# Sheet1.net
KiCad netlist of a schematic drawn in Altium Designer
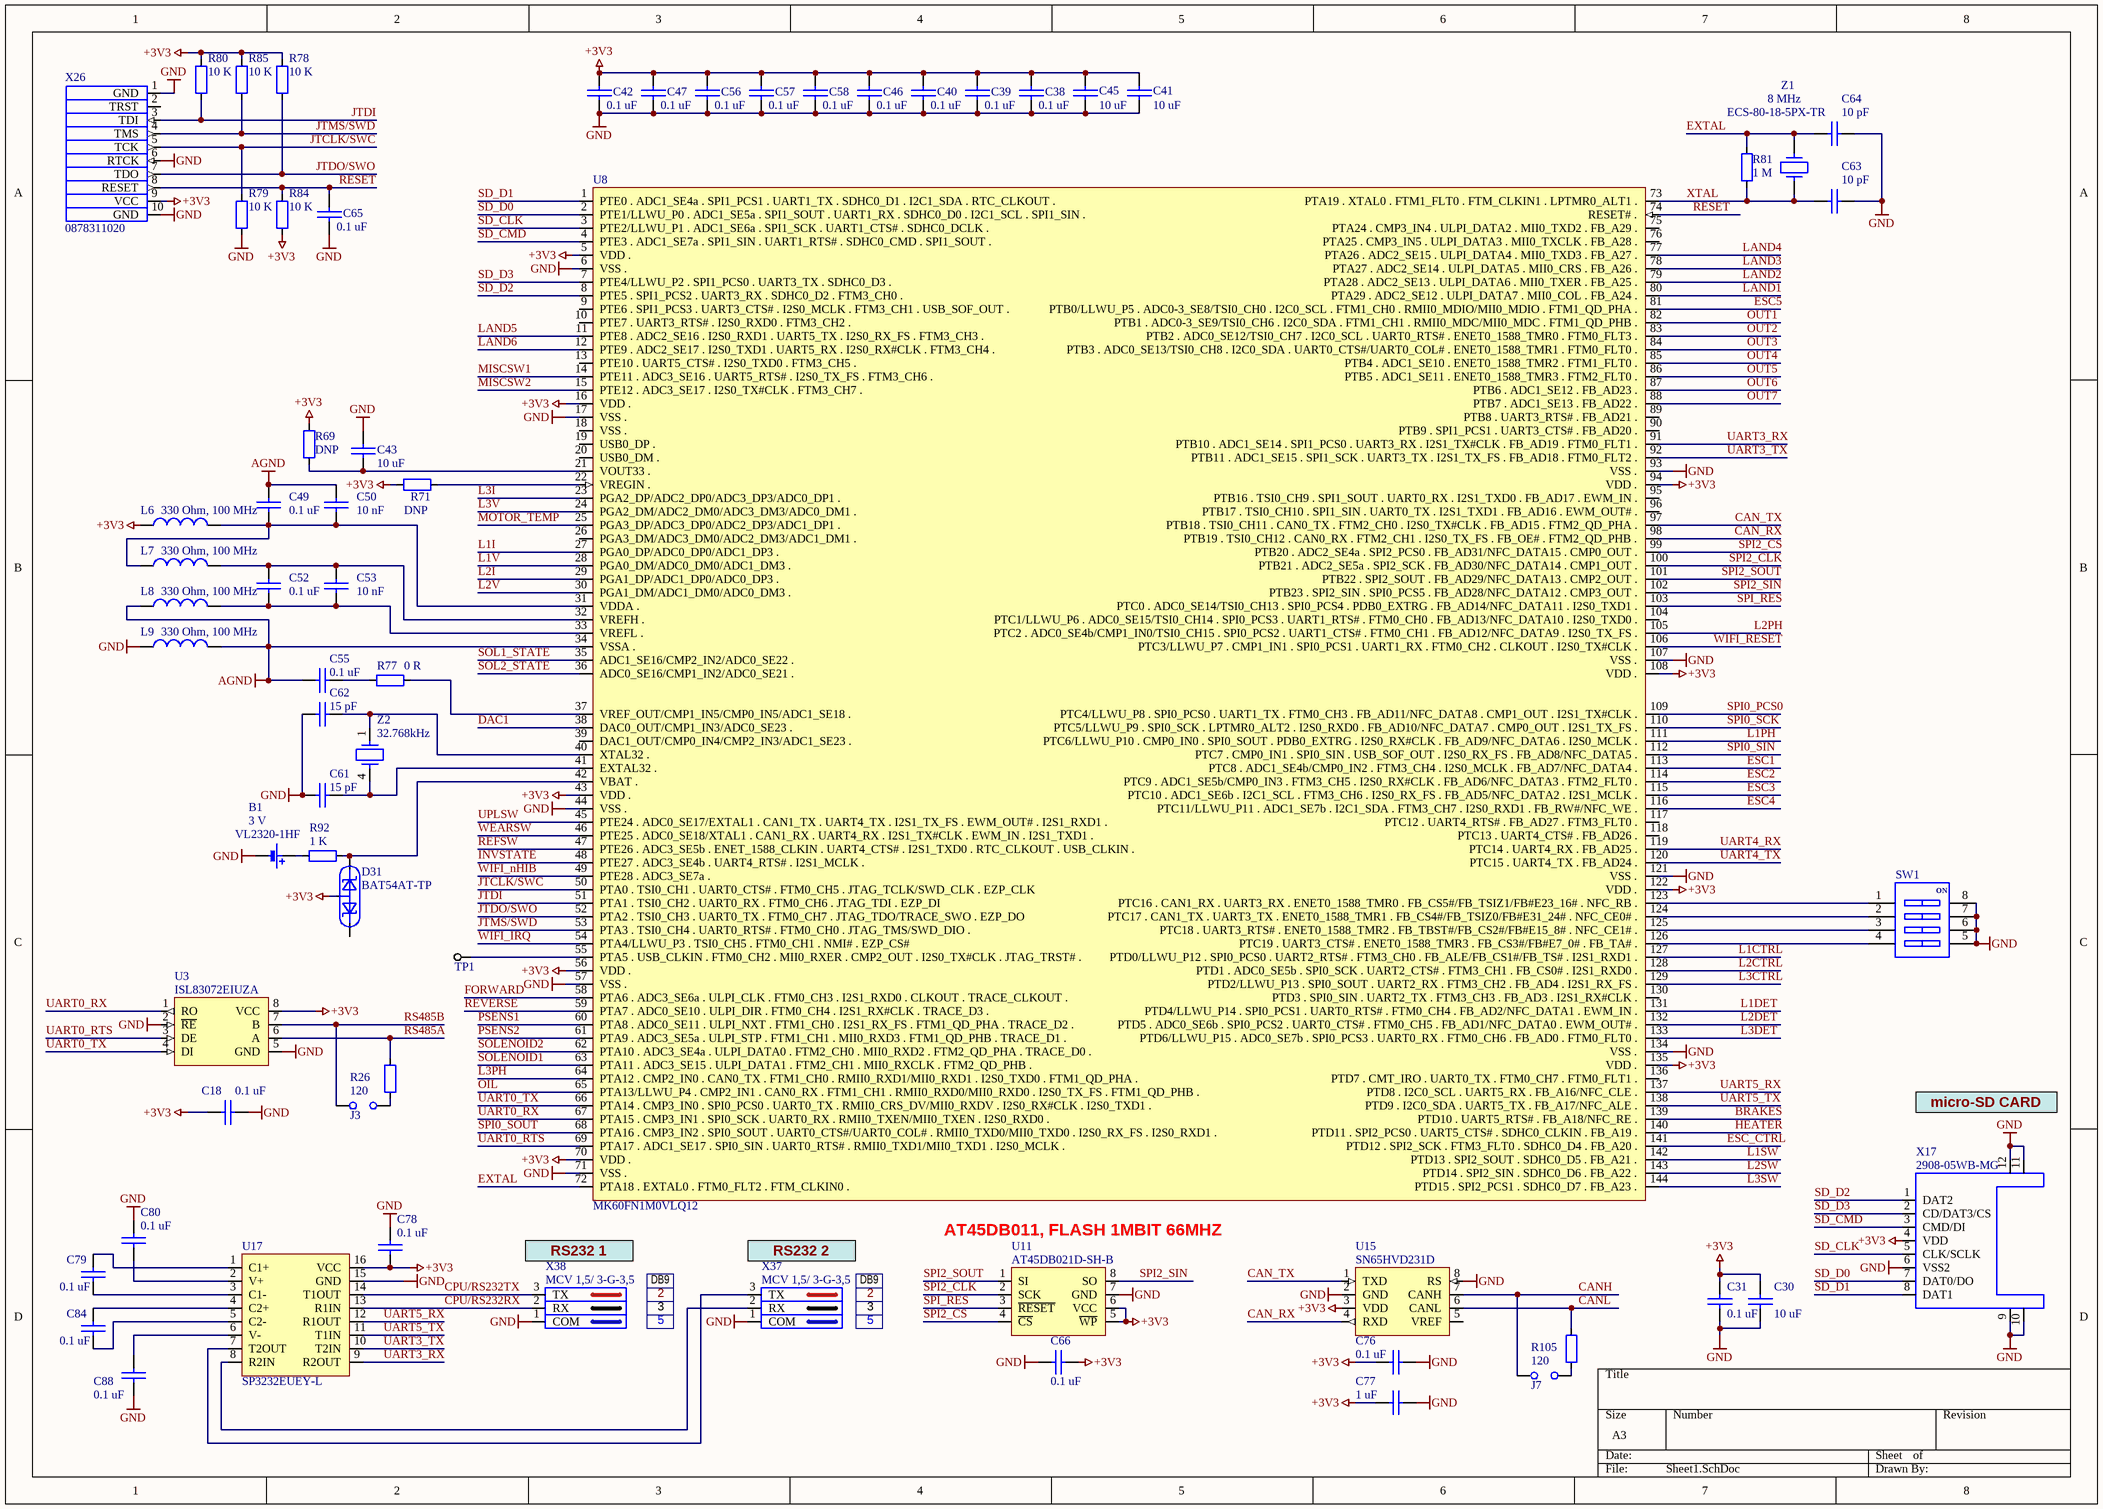
[diagram p0: Sheet1.SchDoc]

(export (version "E")
  (design (tool "Eeschema 10.0.6"))
  (components
    (comp (ref "B1")
      (value "VL2320-1HF")
      (footprint "SANYO ML2430")
      (description "Rechargeable Litium battery, Sanyo, 100 mAh, 3.1 V")
      (fields
        (field (name "PARTNUM") "P083-ND")
        (field (name "MANUFACTURER") "Panasonic - BSG")
        (field (name "ALTIUM_VALUE") "3 V")
      )
      (libsource (lib "*") (part "VL2320-1HF"))
    )
    (comp (ref "C18")
      (value "0.1 uF")
      (footprint "1608[0603]")
      (description "0.1 uF, 25V, 10% , X7R,  0603 SMD MLC Capacitor")
      (fields (field (name "TOLERANCE") "10%") (field (name "MANUFACTURER") "SAMSUNG"))
      (libsource (lib "ea_Capacitors") (part "CVNF100K0603-25"))
    )
    (comp (ref "C30")
      (value "10 uF")
      (footprint "2012[0805]")
      (description "10 uF, 16V, X5R, ±10%, 0805")
      (fields (field (name "MANUFACTURER") "TDK Corporation") (field (name "TOLERANCE") "±10%"))
      (libsource (lib "ea_Capacitors") (part "C2012X5R1C106K/0.85"))
    )
    (comp (ref "C31")
      (value "0.1 uF")
      (footprint "1608[0603]")
      (description "0.1 uF, 25V, 10% , X7R,  0603 SMD MLC Capacitor")
      (fields (field (name "TOLERANCE") "10%") (field (name "MANUFACTURER") "SAMSUNG"))
      (libsource (lib "ea_Capacitors") (part "CVNF100K0603-25"))
    )
    (comp (ref "C38")
      (value "0.1 uF")
      (footprint "1608[0603]")
      (description "0.1 uF, 25V, 10% , X7R,  0603 SMD MLC Capacitor")
      (fields (field (name "TOLERANCE") "10%") (field (name "MANUFACTURER") "SAMSUNG"))
      (libsource (lib "ea_Capacitors") (part "CVNF100K0603-25"))
    )
    (comp (ref "C39")
      (value "0.1 uF")
      (footprint "1608[0603]")
      (description "0.1 uF, 25V, 10% , X7R,  0603 SMD MLC Capacitor")
      (fields (field (name "TOLERANCE") "10%") (field (name "MANUFACTURER") "SAMSUNG"))
      (libsource (lib "ea_Capacitors") (part "CVNF100K0603-25"))
    )
    (comp (ref "C40")
      (value "0.1 uF")
      (footprint "1608[0603]")
      (description "0.1 uF, 25V, 10% , X7R,  0603 SMD MLC Capacitor")
      (fields (field (name "TOLERANCE") "10%") (field (name "MANUFACTURER") "SAMSUNG"))
      (libsource (lib "ea_Capacitors") (part "CVNF100K0603-25"))
    )
    (comp (ref "C41")
      (value "10 uF")
      (footprint "2012[0805]")
      (description "10 uF, 16V, X5R, ±10%, 0805")
      (fields (field (name "MANUFACTURER") "TDK Corporation") (field (name "TOLERANCE") "±10%"))
      (libsource (lib "ea_Capacitors") (part "C2012X5R1C106K/0.85"))
    )
    (comp (ref "C42")
      (value "0.1 uF")
      (footprint "1608[0603]")
      (description "0.1 uF, 25V, 10% , X7R,  0603 SMD MLC Capacitor")
      (fields (field (name "TOLERANCE") "10%") (field (name "MANUFACTURER") "SAMSUNG"))
      (libsource (lib "ea_Capacitors") (part "CVNF100K0603-25"))
    )
    (comp (ref "C43")
      (value "10 uF")
      (footprint "2012[0805]")
      (description "10 uF, 16V, X5R, ±10%, 0805")
      (fields (field (name "MANUFACTURER") "TDK Corporation") (field (name "TOLERANCE") "±10%"))
      (libsource (lib "ea_Capacitors") (part "C2012X5R1C106K/0.85"))
    )
    (comp (ref "C45")
      (value "10 uF")
      (footprint "2012[0805]")
      (description "10 uF, 16V, X5R, ±10%, 0805")
      (fields (field (name "MANUFACTURER") "TDK Corporation") (field (name "TOLERANCE") "±10%"))
      (libsource (lib "ea_Capacitors") (part "C2012X5R1C106K/0.85"))
    )
    (comp (ref "C46")
      (value "0.1 uF")
      (footprint "1608[0603]")
      (description "0.1 uF, 25V, 10% , X7R,  0603 SMD MLC Capacitor")
      (fields (field (name "TOLERANCE") "10%") (field (name "MANUFACTURER") "SAMSUNG"))
      (libsource (lib "ea_Capacitors") (part "CVNF100K0603-25"))
    )
    (comp (ref "C47")
      (value "0.1 uF")
      (footprint "1608[0603]")
      (description "0.1 uF, 25V, 10% , X7R,  0603 SMD MLC Capacitor")
      (fields (field (name "TOLERANCE") "10%") (field (name "MANUFACTURER") "SAMSUNG"))
      (libsource (lib "ea_Capacitors") (part "CVNF100K0603-25"))
    )
    (comp (ref "C49")
      (value "0.1 uF")
      (footprint "1608[0603]")
      (description "0.1 uF, 25V, 10% , X7R,  0603 SMD MLC Capacitor")
      (fields (field (name "TOLERANCE") "10%") (field (name "MANUFACTURER") "SAMSUNG"))
      (libsource (lib "ea_Capacitors") (part "CVNF100K0603-25"))
    )
    (comp (ref "C50")
      (value "10 nF")
      (footprint "1608[0603]")
      (description "10 nF, 50V, 5%, X7R, 0603 SMD MLC Capacitor")
      (fields (field (name "TOLERANCE") "5%") (field (name "MANUFACTURER") "SAMSUNG"))
      (libsource (lib "ea_Capacitors") (part "CVNF010K0603"))
    )
    (comp (ref "C52")
      (value "0.1 uF")
      (footprint "1608[0603]")
      (description "0.1 uF, 25V, 10% , X7R,  0603 SMD MLC Capacitor")
      (fields (field (name "TOLERANCE") "10%") (field (name "MANUFACTURER") "SAMSUNG"))
      (libsource (lib "ea_Capacitors") (part "CVNF100K0603-25"))
    )
    (comp (ref "C53")
      (value "10 nF")
      (footprint "1608[0603]")
      (description "10 nF, 50V, 5%, X7R, 0603 SMD MLC Capacitor")
      (fields (field (name "TOLERANCE") "5%") (field (name "MANUFACTURER") "SAMSUNG"))
      (libsource (lib "ea_Capacitors") (part "CVNF010K0603"))
    )
    (comp (ref "C55")
      (value "0.1 uF")
      (footprint "1608[0603]")
      (description "0.1 uF, 25V, 10% , X7R,  0603 SMD MLC Capacitor")
      (fields (field (name "TOLERANCE") "10%") (field (name "MANUFACTURER") "SAMSUNG"))
      (libsource (lib "ea_Capacitors") (part "CVNF100K0603-25"))
    )
    (comp (ref "C56")
      (value "0.1 uF")
      (footprint "1608[0603]")
      (description "0.1 uF, 25V, 10% , X7R,  0603 SMD MLC Capacitor")
      (fields (field (name "TOLERANCE") "10%") (field (name "MANUFACTURER") "SAMSUNG"))
      (libsource (lib "ea_Capacitors") (part "CVNF100K0603-25"))
    )
    (comp (ref "C57")
      (value "0.1 uF")
      (footprint "1608[0603]")
      (description "0.1 uF, 25V, 10% , X7R,  0603 SMD MLC Capacitor")
      (fields (field (name "TOLERANCE") "10%") (field (name "MANUFACTURER") "SAMSUNG"))
      (libsource (lib "ea_Capacitors") (part "CVNF100K0603-25"))
    )
    (comp (ref "C58")
      (value "0.1 uF")
      (footprint "1608[0603]")
      (description "0.1 uF, 25V, 10% , X7R,  0603 SMD MLC Capacitor")
      (fields (field (name "TOLERANCE") "10%") (field (name "MANUFACTURER") "SAMSUNG"))
      (libsource (lib "ea_Capacitors") (part "CVNF100K0603-25"))
    )
    (comp (ref "C61")
      (value "15 pF")
      (footprint "1608[0603]")
      (description "15 pF, 50V, 5%, NP0, 0603 SMD MLC Capacitor")
      (fields (field (name "MANUFACTURER") "YAGEO AMERICA CORPORATION") (field (name "TOLERANCE") "5%"))
      (libsource (lib "ea_Capacitors") (part "CCPF015K0603"))
    )
    (comp (ref "C62")
      (value "15 pF")
      (footprint "1608[0603]")
      (description "15 pF, 50V, 5%, NP0, 0603 SMD MLC Capacitor")
      (fields (field (name "MANUFACTURER") "YAGEO AMERICA CORPORATION") (field (name "TOLERANCE") "5%"))
      (libsource (lib "ea_Capacitors") (part "CCPF015K0603"))
    )
    (comp (ref "C63")
      (value "10 pF")
      (footprint "1608[0603]")
      (description "10 pF, 50V, 5%, NP0, 0603 SMD MLC Capacitor")
      (fields (field (name "MANUFACTURER") "Kemet") (field (name "TOLERANCE") "5%"))
      (libsource (lib "ea_Capacitors") (part "CCPF010K0603"))
    )
    (comp (ref "C64")
      (value "10 pF")
      (footprint "1608[0603]")
      (description "10 pF, 50V, 5%, NP0, 0603 SMD MLC Capacitor")
      (fields (field (name "MANUFACTURER") "Kemet") (field (name "TOLERANCE") "5%"))
      (libsource (lib "ea_Capacitors") (part "CCPF010K0603"))
    )
    (comp (ref "C65")
      (value "0.1 uF")
      (footprint "1608[0603]")
      (description "0.1 uF, 25V, 10% , X7R,  0603 SMD MLC Capacitor")
      (fields (field (name "TOLERANCE") "10%") (field (name "MANUFACTURER") "SAMSUNG"))
      (libsource (lib "ea_Capacitors") (part "CVNF100K0603-25"))
    )
    (comp (ref "C66")
      (value "0.1 uF")
      (footprint "1608[0603]")
      (description "0.1 uF, 25V, 10% , X7R,  0603 SMD MLC Capacitor")
      (fields (field (name "TOLERANCE") "10%") (field (name "MANUFACTURER") "SAMSUNG"))
      (libsource (lib "ea_Capacitors") (part "CVNF100K0603-25"))
    )
    (comp (ref "C76")
      (value "0.1 uF")
      (footprint "1608[0603]")
      (description "0.1 uF, 25V, 10% , X7R,  0603 SMD MLC Capacitor")
      (fields (field (name "TOLERANCE") "10%") (field (name "MANUFACTURER") "SAMSUNG"))
      (libsource (lib "ea_Capacitors") (part "CVNF100K0603-25"))
    )
    (comp (ref "C77")
      (value "1 uF")
      (footprint "1608[0603]")
      (description "1.0 uF, 6.3V, 10%, X5R, 0603")
      (fields
        (field (name "TOLERANCE") "+-10%")
        (field (name "MANUFACTURER") "Murata Electronics North America")
      )
      (libsource (lib "*") (part "GRM188R60J105KA01D"))
    )
    (comp (ref "C78")
      (value "0.1 uF")
      (footprint "1608[0603]")
      (description "0.1 uF, 25V, 10% , X7R,  0603 SMD MLC Capacitor")
      (fields (field (name "TOLERANCE") "10%") (field (name "MANUFACTURER") "SAMSUNG"))
      (libsource (lib "ea_Capacitors") (part "CVNF100K0603-25"))
    )
    (comp (ref "C79")
      (value "0.1 uF")
      (footprint "1608[0603]")
      (description "0.1 uF, 25V, 10% , X7R,  0603 SMD MLC Capacitor")
      (fields (field (name "TOLERANCE") "10%") (field (name "MANUFACTURER") "SAMSUNG"))
      (libsource (lib "ea_Capacitors") (part "CVNF100K0603-25"))
    )
    (comp (ref "C80")
      (value "0.1 uF")
      (footprint "1608[0603]")
      (description "0.1 uF, 25V, 10% , X7R,  0603 SMD MLC Capacitor")
      (fields (field (name "TOLERANCE") "10%") (field (name "MANUFACTURER") "SAMSUNG"))
      (libsource (lib "ea_Capacitors") (part "CVNF100K0603-25"))
    )
    (comp (ref "C84")
      (value "0.1 uF")
      (footprint "1608[0603]")
      (description "0.1 uF, 25V, 10% , X7R,  0603 SMD MLC Capacitor")
      (fields (field (name "TOLERANCE") "10%") (field (name "MANUFACTURER") "SAMSUNG"))
      (libsource (lib "ea_Capacitors") (part "CVNF100K0603-25"))
    )
    (comp (ref "C88")
      (value "0.1 uF")
      (footprint "1608[0603]")
      (description "0.1 uF, 25V, 10% , X7R,  0603 SMD MLC Capacitor")
      (fields (field (name "TOLERANCE") "10%") (field (name "MANUFACTURER") "SAMSUNG"))
      (libsource (lib "ea_Capacitors") (part "CVNF100K0603-25"))
    )
    (comp (ref "D31")
      (value "BAT54AT-TP")
      (footprint "SOT-523F")
      (description "Schottky Diode, 30 V, 200 mA, common anode, SOT523")
      (fields (field (name "MANUFACTURER") "Micro Commercial Co") (field (name "PARTNUM") "BAT54AT-TPDKR-ND"))
      (libsource (lib "ea_Diodes") (part "BAT54AT-TP"))
    )
    (comp (ref "J3")
      (value "PH1-02-TA-HT")
      (footprint "HDR1X2V")
      (description "2 Pos. 2.54 mm Single Row Through Hole Straight Pin Header")
      (fields (field (name "MANUFACTURER") "ADAM TECH"))
      (libsource (lib "ea_Commutation") (part "Jumper"))
    )
    (comp (ref "J7")
      (value "PH1-02-TA-HT")
      (footprint "HDR1X2V")
      (description "2 Pos. 2.54 mm Single Row Through Hole Straight Pin Header")
      (fields (field (name "MANUFACTURER") "ADAM TECH"))
      (libsource (lib "ea_Commutation") (part "Jumper"))
    )
    (comp (ref "L6")
      (value "330 Ohm, 100 MHz")
      (footprint "0603")
      (description "Ferrite bead, 330 Ohm, 100 MHz,  1.5 A, 0.07 Ohm")
      (fields
        (field (name "MANUFACTURER") "Murata Electronics North America")
        (field (name "PARTNUM") "BLM18SG331TN1D")
      )
      (libsource (lib "*") (part "BLM18SG331TN1D"))
    )
    (comp (ref "L7")
      (value "330 Ohm, 100 MHz")
      (footprint "0603")
      (description "Ferrite bead, 330 Ohm, 100 MHz,  1.5 A, 0.07 Ohm")
      (fields
        (field (name "MANUFACTURER") "Murata Electronics North America")
        (field (name "PARTNUM") "BLM18SG331TN1D")
      )
      (libsource (lib "*") (part "BLM18SG331TN1D"))
    )
    (comp (ref "L8")
      (value "330 Ohm, 100 MHz")
      (footprint "0603")
      (description "Ferrite bead, 330 Ohm, 100 MHz,  1.5 A, 0.07 Ohm")
      (fields
        (field (name "MANUFACTURER") "Murata Electronics North America")
        (field (name "PARTNUM") "BLM18SG331TN1D")
      )
      (libsource (lib "*") (part "BLM18SG331TN1D"))
    )
    (comp (ref "L9")
      (value "330 Ohm, 100 MHz")
      (footprint "0603")
      (description "Ferrite bead, 330 Ohm, 100 MHz,  1.5 A, 0.07 Ohm")
      (fields
        (field (name "MANUFACTURER") "Murata Electronics North America")
        (field (name "PARTNUM") "BLM18SG331TN1D")
      )
      (libsource (lib "*") (part "BLM18SG331TN1D"))
    )
    (comp (ref "R26")
      (value "120")
      (footprint "0603")
      (description "120 R, 1%, 0603, SMD Resistor, Taped")
      (fields (field (name "MANUFACTURER") "Vishay") (field (name "TOLERANCE") "1%"))
      (libsource (lib "ea_Resistors") (part "RL0603E120-1"))
    )
    (comp (ref "R69")
      (value "DNP")
      (footprint "0603")
      (description "DNP, 0603")
      (fields (field (name "Comment") "DNP_0603"))
      (libsource (lib "ea_Resistors") (part "DNP_0603"))
    )
    (comp (ref "R71")
      (value "DNP")
      (footprint "0603")
      (description "DNP, 0603")
      (fields (field (name "Comment") "DNP_0603"))
      (libsource (lib "") (part "DNP_0603_1"))
    )
    (comp (ref "R77")
      (value "0 R")
      (footprint "0603")
      (description "0 R, 5%, 0603, SMD Resistor, Taped")
      (fields (field (name "MANUFACTURER") "YAGEO AMERICA CORPORATION") (field (name "TOLERANCE") "5%"))
      (libsource (lib "ea_Resistors") (part "RL0603E000"))
    )
    (comp (ref "R78")
      (value "10 K")
      (footprint "0603")
      (description "10 K, 1%, 0603, SMD Resistor, Taped")
      (fields (field (name "MANUFACTURER") "Vishay Dale") (field (name "TOLERANCE") "1%"))
      (libsource (lib "ea_Resistors") (part "RL0603K010-1"))
    )
    (comp (ref "R79")
      (value "10 K")
      (footprint "0603")
      (description "10 K, 1%, 0603, SMD Resistor, Taped")
      (fields (field (name "MANUFACTURER") "Vishay Dale") (field (name "TOLERANCE") "1%"))
      (libsource (lib "ea_Resistors") (part "RL0603K010-1"))
    )
    (comp (ref "R80")
      (value "10 K")
      (footprint "0603")
      (description "10 K, 1%, 0603, SMD Resistor, Taped")
      (fields (field (name "MANUFACTURER") "Vishay Dale") (field (name "TOLERANCE") "1%"))
      (libsource (lib "ea_Resistors") (part "RL0603K010-1"))
    )
    (comp (ref "R81")
      (value "1 M")
      (footprint "0603")
      (description "1 M, 1%, 0603, SMD Resistor, Taped")
      (fields (field (name "MANUFACTURER") "YAGEO AMERICA CORPORATION") (field (name "TOLERANCE") "1%"))
      (libsource (lib "ea_Resistors") (part "RC0603FR-071ML"))
    )
    (comp (ref "R84")
      (value "10 K")
      (footprint "0603")
      (description "10 K, 1%, 0603, SMD Resistor, Taped")
      (fields (field (name "MANUFACTURER") "Vishay Dale") (field (name "TOLERANCE") "1%"))
      (libsource (lib "ea_Resistors") (part "RL0603K010-1"))
    )
    (comp (ref "R85")
      (value "10 K")
      (footprint "0603")
      (description "10 K, 1%, 0603, SMD Resistor, Taped")
      (fields (field (name "MANUFACTURER") "Vishay Dale") (field (name "TOLERANCE") "1%"))
      (libsource (lib "ea_Resistors") (part "RL0603K010-1"))
    )
    (comp (ref "R92")
      (value "1 K")
      (footprint "0603")
      (description "1 K, 1%, 0603, SMD Resistor, Taped")
      (fields (field (name "MANUFACTURER") "YAGEO AMERICA CORPORATION") (field (name "TOLERANCE") "1%"))
      (libsource (lib "ea_Resistors") (part "RL0603K001-1"))
    )
    (comp (ref "R105")
      (value "120")
      (footprint "0603")
      (description "120 R, 1%, 0603, SMD Resistor, Taped")
      (fields (field (name "MANUFACTURER") "Vishay") (field (name "TOLERANCE") "1%"))
      (libsource (lib "ea_Resistors") (part "RL0603E120-1"))
    )
    (comp (ref "SW1")
      (value "MCDHN-04F-T-V")
      (footprint "MCDHN-04F-T-V")
      (description "SWITCH, DIP, SMD, 4 WAY, 1.27mm")
      (fields (field (name "MANUFACTURER") "MULTICOMP") (field (name "PARTNUM") "1605479"))
      (libsource (lib "ea_Commutation") (part "MCDHN-04F-T-V"))
    )
    (comp (ref "TP1")
      (value "Test_point 0.7 мм")
      (footprint "Test point 0.7 мм")
      (libsource (lib "ea_Connectors") (part "Test_point 0.7 мм"))
    )
    (comp (ref "U3")
      (value "ISL83072EIUZA")
      (footprint "MSOP 8")
      (description "RS485/422 Transc. 3..3.6V  , -40..+85 C,10-MSOP")
      (fields (field (name "MANUFACTURER") "Intersil") (field (name "PARTNUM") "ISL83072EIUZA-TCT-ND"))
      (libsource (lib "ea_IC_Interfaces") (part "ISL3178EIUZ"))
    )
    (comp (ref "U8")
      (value "MK60FN1M0VLQ12")
      (footprint "ea_TQFP:LQFP144")
      (description "MK60 Series 32 Bit 1 MB Flash 128 KB Ram 120 Mhz Microcontroller - LQFP-144")
      (fields (field (name "MANUFACTURER") "Freescale"))
      (libsource (lib "ea_IC_CPU") (part "MK60FN1M0VLQ12"))
    )
    (comp (ref "U11")
      (value "AT45DB021D-SH-B")
      (footprint "SO-8  wide")
      (description "IC DATAFLASH 1MBIT 2.7 V ~ 3.6 V 8-SOIC")
      (fields (field (name "MANUFACTURER") "Adesto Technologies") (field (name "PARTNUM") "1265-1033-1-ND"))
      (libsource (lib "ea_IC_NOR_NAND_FLASH") (part "AT45DB011D-SH-T"))
    )
    (comp (ref "U15")
      (value "SN65HVD231D")
      (footprint "SO-8")
      (description "3.3-V CAN TRANSCEIVERS SO-8")
      (fields (field (name "MANUFACTURER") "Texas Instruments") (field (name "PARTNUM") "296-12206-5-ND"))
      (libsource (lib "ea_IC_Interfaces") (part "SN65HVD231D"))
    )
    (comp (ref "U17")
      (value "SP3232EUEY-L")
      (footprint "TSOP65P640-16AM")
      (description "IC TXRX RS232 ESD TRUE, 1 Mbps, -40+85C, 16TSSOP")
      (fields (field (name "MANUFACTURER") "Exar Corporation") (field (name "PARTNUM") "1016-1510-5-ND"))
      (libsource (lib "ea_IC_Interfaces") (part "SP3232EUEY-L"))
    )
    (comp (ref "X17")
      (value "2908-05WB-MG")
      (footprint "2908-05WB-MG")
      (description "microSD cadr holder")
      (fields
        (field (name "MANUFACTURER") "Amphenol Commercial Products")
        (field (name "PARTNUM") "101-00660-68-6-1-ND")
      )
      (libsource (lib "ea_CARD_holders") (part "2908-05WB-MG"))
    )
    (comp (ref "X26")
      (value "0878311020")
      (footprint "878311020 MGRID WALL HDR SMD")
      (description "JTAG, CONN HEADER 10POS 2MM VERT SMD")
      (fields (field (name "MANUFACTURER") "Molex Inc") (field (name "PARTNUM") "WM18639-ND"))
      (libsource (lib "ea_Connectors") (part "0878321020"))
    )
    (comp (ref "X37")
      (value "MCV 1,5/ 3-G-3,5")
      (footprint "mcv1.5-3-g_3.5")
      (description "Header, 8 A, 160 V, 3.5 mm pitch, 3 pos")
      (fields (field (name "MANUFACTURER") "Phoenix Contact") (field (name "PARTNUM") "1843619"))
      (libsource (lib "ea_Connectors") (part "MCV1.5/3-G-3.5"))
    )
    (comp (ref "X38")
      (value "MCV 1,5/ 3-G-3,5")
      (footprint "mcv1.5-3-g_3.5")
      (description "Header, 8 A, 160 V, 3.5 mm pitch, 3 pos")
      (fields (field (name "MANUFACTURER") "Phoenix Contact") (field (name "PARTNUM") "1843619"))
      (libsource (lib "ea_Connectors") (part "MCV1.5/3-G-3.5"))
    )
    (comp (ref "Z1")
      (value "ECS-80-18-5PX-TR")
      (footprint "Quartz Crystal SMU4")
      (fields
        (field (name "MANUFACTURER") "ECS Inc.")
        (field (name "ALTIUM_VALUE") "8 MHz")
        (field (name "PARTNUM") "XC1271CT-ND")
      )
      (libsource (lib "*") (part "ECS-80-18-5PX-TR"))
    )
    (comp (ref "Z2")
      (value "32.768kHz")
      (footprint "CM200S")
      (description "Crystal 32.768 kHz ±20 ppm 6 pF -40 to +85 °C SMT Tuning Fork Crystal")
      (fields
        (field (name "MANUFACTURER") "CITIZEN FINETECH MIYOTA")
        (field (name "PARTNUM") "CM200C32768DZBT")
      )
      (libsource (lib "*") (part "MC306-32,768"))
    )
  )
  (nets
    (net (code "1") (name "+3V3") (class "Default")
      (node (ref "C18") (pin "1") (pinfunction "1_1") (pintype "passive"))
      (node (ref "C30") (pin "1") (pinfunction "1_1") (pintype "passive"))
      (node (ref "C31") (pin "1") (pinfunction "1_1") (pintype "passive"))
      (node (ref "C38") (pin "2") (pinfunction "2_2") (pintype "passive"))
      (node (ref "C39") (pin "2") (pinfunction "2_2") (pintype "passive"))
      (node (ref "C40") (pin "2") (pinfunction "2_2") (pintype "passive"))
      (node (ref "C41") (pin "1") (pinfunction "1_1") (pintype "passive"))
      (node (ref "C42") (pin "2") (pinfunction "2_2") (pintype "passive"))
      (node (ref "C45") (pin "1") (pinfunction "1_1") (pintype "passive"))
      (node (ref "C46") (pin "2") (pinfunction "2_2") (pintype "passive"))
      (node (ref "C47") (pin "2") (pinfunction "2_2") (pintype "passive"))
      (node (ref "C56") (pin "2") (pinfunction "2_2") (pintype "passive"))
      (node (ref "C57") (pin "2") (pinfunction "2_2") (pintype "passive"))
      (node (ref "C58") (pin "2") (pinfunction "2_2") (pintype "passive"))
      (node (ref "C66") (pin "1") (pinfunction "1_1") (pintype "passive"))
      (node (ref "C76") (pin "1") (pinfunction "1_1") (pintype "passive"))
      (node (ref "C77") (pin "1") (pinfunction "1_1") (pintype "passive"))
      (node (ref "C78") (pin "1") (pinfunction "1_1") (pintype "passive"))
      (node (ref "D31") (pin "3") (pintype "passive"))
      (node (ref "L6") (pin "1") (pinfunction "1_1") (pintype "passive"))
      (node (ref "R69") (pin "2") (pinfunction "2_2") (pintype "passive"))
      (node (ref "R71") (pin "1") (pinfunction "1_1") (pintype "passive"))
      (node (ref "R78") (pin "2") (pinfunction "2_2") (pintype "passive"))
      (node (ref "R80") (pin "2") (pinfunction "2_2") (pintype "passive"))
      (node (ref "R84") (pin "1") (pinfunction "1_1") (pintype "passive"))
      (node (ref "R85") (pin "2") (pinfunction "2_2") (pintype "passive"))
      (node (ref "U11") (pin "5") (pinfunction "~{WP}_5") (pintype "passive"))
      (node (ref "U11") (pin "6") (pinfunction "VCC_6") (pintype "passive"))
      (node (ref "U15") (pin "3") (pinfunction "VDD_3") (pintype "power_in"))
      (node (ref "U17") (pin "16") (pinfunction "VCC_16") (pintype "passive"))
      (node (ref "U3") (pin "8") (pinfunction "VCC_8") (pintype "power_in"))
      (node (ref "U8") (pin "108") (pinfunction "VDD_._108") (pintype "power_in"))
      (node (ref "U8") (pin "122") (pinfunction "VDD_._122") (pintype "power_in"))
      (node (ref "U8") (pin "135") (pinfunction "VDD_._135") (pintype "power_in"))
      (node (ref "U8") (pin "16") (pinfunction "VDD_._16") (pintype "power_in"))
      (node (ref "U8") (pin "43") (pinfunction "VDD_._43") (pintype "power_in"))
      (node (ref "U8") (pin "5") (pinfunction "VDD_._5") (pintype "power_in"))
      (node (ref "U8") (pin "56") (pinfunction "VDD_._56") (pintype "power_in"))
      (node (ref "U8") (pin "70") (pinfunction "VDD_._70") (pintype "power_in"))
      (node (ref "U8") (pin "94") (pinfunction "VDD_._94") (pintype "power_in"))
      (node (ref "X17") (pin "4") (pinfunction "VDD_4") (pintype "passive"))
      (node (ref "X26") (pin "9") (pinfunction "VCC_9") (pintype "power_in"))
    )
    (net (code "2") (name "/BRAKES") (class "Default")
      (node (ref "U8") (pin "139") (pinfunction "PTD10_._UART5_RTS#_._FB_A18/NFC_RE_._139") (pintype "bidirectional"))
    )
    (net (code "3") (name "/CANH") (class "Default")
      (node (ref "J7") (pin "1") (pinfunction "1_1") (pintype "passive"))
      (node (ref "U15") (pin "7") (pinfunction "CANH_7") (pintype "bidirectional"))
    )
    (net (code "4") (name "/CANL") (class "Default")
      (node (ref "R105") (pin "2") (pinfunction "2_2") (pintype "passive"))
      (node (ref "U15") (pin "6") (pinfunction "CANL_6") (pintype "bidirectional"))
    )
    (net (code "5") (name "/CAN_RX") (class "Default")
      (node (ref "U15") (pin "4") (pinfunction "RXD_4") (pintype "output"))
      (node (ref "U8") (pin "98") (pinfunction "PTB19_._TSI0_CH12_._CAN0_RX_._FTM2_CH1_._I2S0_TX_FS_._FB_OE#_._FTM2_QD_PHB_._98") (pintype "bidirectional"))
    )
    (net (code "6") (name "/CAN_TX") (class "Default")
      (node (ref "U15") (pin "1") (pinfunction "TXD_1") (pintype "input"))
      (node (ref "U8") (pin "97") (pinfunction "PTB18_._TSI0_CH11_._CAN0_TX_._FTM2_CH0_._I2S0_TX#CLK_._FB_AD15_._FTM2_QD_PHA_._97") (pintype "bidirectional"))
    )
    (net (code "7") (name "/CPU{slash}RS232RX") (class "Default")
      (node (ref "U17") (pin "13") (pinfunction "R1IN_13") (pintype "passive"))
      (node (ref "X38") (pin "2") (pinfunction "RX_2") (pintype "passive"))
    )
    (net (code "8") (name "/CPU{slash}RS232TX") (class "Default")
      (node (ref "U17") (pin "14") (pinfunction "T1OUT_14") (pintype "passive"))
      (node (ref "X38") (pin "3") (pinfunction "TX_3") (pintype "passive"))
    )
    (net (code "9") (name "/DAC1") (class "Default")
      (node (ref "U8") (pin "38") (pinfunction "DAC0_OUT/CMP1_IN3/ADC0_SE23_._38") (pintype "bidirectional"))
    )
    (net (code "10") (name "/ESC1") (class "Default")
      (node (ref "U8") (pin "113") (pinfunction "PTC8_._ADC1_SE4b/CMP0_IN2_._FTM3_CH4_._I2S0_MCLK_._FB_AD7/NFC_DATA4_._113") (pintype "bidirectional"))
    )
    (net (code "11") (name "/ESC2") (class "Default")
      (node (ref "U8") (pin "114") (pinfunction "PTC9_._ADC1_SE5b/CMP0_IN3_._FTM3_CH5_._I2S0_RX#CLK_._FB_AD6/NFC_DATA3_._FTM2_FLT0_._114") (pintype "bidirectional"))
    )
    (net (code "12") (name "/ESC3") (class "Default")
      (node (ref "U8") (pin "115") (pinfunction "PTC10_._ADC1_SE6b_._I2C1_SCL_._FTM3_CH6_._I2S0_RX_FS_._FB_AD5/NFC_DATA2_._I2S1_MCLK_._115") (pintype "bidirectional"))
    )
    (net (code "13") (name "/ESC4") (class "Default")
      (node (ref "U8") (pin "116") (pinfunction "PTC11/LLWU_P11_._ADC1_SE7b_._I2C1_SDA_._FTM3_CH7_._I2S0_RXD1_._FB_RW#/NFC_WE_._116") (pintype "bidirectional"))
    )
    (net (code "14") (name "/ESC5") (class "Default")
      (node (ref "U8") (pin "81") (pinfunction "PTB0/LLWU_P5_._ADC0-3_SE8/TSI0_CH0_._I2C0_SCL_._FTM1_CH0_._RMII0_MDIO/MII0_MDIO_._FTM1_QD_PHA_._81") (pintype "bidirectional"))
    )
    (net (code "15") (name "/ESC_CTRL") (class "Default")
      (node (ref "U8") (pin "141") (pinfunction "PTD12_._SPI2_SCK_._FTM3_FLT0_._SDHC0_D4_._FB_A20_._141") (pintype "bidirectional"))
    )
    (net (code "16") (name "/EXTAL") (class "Default")
      (node (ref "C64") (pin "1") (pinfunction "1_1") (pintype "passive"))
      (node (ref "R81") (pin "2") (pinfunction "2_2") (pintype "passive"))
      (node (ref "U8") (pin "72") (pinfunction "PTA18_._EXTAL0_._FTM0_FLT2_._FTM_CLKIN0_._72") (pintype "bidirectional"))
      (node (ref "Z1") (pin "2") (pinfunction "2_2") (pintype "passive"))
    )
    (net (code "17") (name "/FORWARD") (class "Default")
      (node (ref "U8") (pin "58") (pinfunction "PTA6_._ADC3_SE6a_._ULPI_CLK_._FTM0_CH3_._I2S1_RXD0_._CLKOUT_._TRACE_CLKOUT_._58") (pintype "bidirectional"))
    )
    (net (code "18") (name "/HEATER") (class "Default")
      (node (ref "U8") (pin "140") (pinfunction "PTD11_._SPI2_PCS0_._UART5_CTS#_._SDHC0_CLKIN_._FB_A19_._140") (pintype "bidirectional"))
    )
    (net (code "19") (name "/INVSTATE") (class "Default")
      (node (ref "U8") (pin "48") (pinfunction "PTE27_._ADC3_SE4b_._UART4_RTS#_._I2S1_MCLK_._48") (pintype "bidirectional"))
    )
    (net (code "20") (name "/JTCLK{slash}SWC") (class "Default")
      (node (ref "R79") (pin "2") (pinfunction "2_2") (pintype "passive"))
      (node (ref "U8") (pin "50") (pinfunction "PTA0_._TSI0_CH1_._UART0_CTS#_._FTM0_CH5_._JTAG_TCLK/SWD_CLK_._EZP_CLK_50") (pintype "bidirectional"))
      (node (ref "X26") (pin "5") (pinfunction "TCK_5") (pintype "output"))
    )
    (net (code "21") (name "/JTDI") (class "Default")
      (node (ref "R80") (pin "1") (pinfunction "1_1") (pintype "passive"))
      (node (ref "U8") (pin "51") (pinfunction "PTA1_._TSI0_CH2_._UART0_RX_._FTM0_CH6_._JTAG_TDI_._EZP_DI_51") (pintype "bidirectional"))
      (node (ref "X26") (pin "3") (pinfunction "TDI_3") (pintype "input"))
    )
    (net (code "22") (name "/JTDO{slash}SWO") (class "Default")
      (node (ref "R78") (pin "1") (pinfunction "1_1") (pintype "passive"))
      (node (ref "U8") (pin "52") (pinfunction "PTA2_._TSI0_CH3_._UART0_TX_._FTM0_CH7_._JTAG_TDO/TRACE_SWO_._EZP_DO_52") (pintype "bidirectional"))
      (node (ref "X26") (pin "7") (pinfunction "TDO_7") (pintype "output"))
    )
    (net (code "23") (name "/JTMS{slash}SWD") (class "Default")
      (node (ref "R85") (pin "1") (pinfunction "1_1") (pintype "passive"))
      (node (ref "U8") (pin "53") (pinfunction "PTA3_._TSI0_CH4_._UART0_RTS#_._FTM0_CH0_._JTAG_TMS/SWD_DIO_._53") (pintype "bidirectional"))
      (node (ref "X26") (pin "4") (pinfunction "TMS_4") (pintype "output"))
    )
    (net (code "24") (name "/L1CTRL") (class "Default")
      (node (ref "U8") (pin "127") (pinfunction "PTD0/LLWU_P12_._SPI0_PCS0_._UART2_RTS#_._FTM3_CH0_._FB_ALE/FB_CS1#/FB_TS#_._I2S1_RXD1_._127") (pintype "bidirectional"))
    )
    (net (code "25") (name "/L1DET") (class "Default")
      (node (ref "U8") (pin "131") (pinfunction "PTD4/LLWU_P14_._SPI0_PCS1_._UART0_RTS#_._FTM0_CH4_._FB_AD2/NFC_DATA1_._EWM_IN_._131") (pintype "bidirectional"))
    )
    (net (code "26") (name "/L1I") (class "Default")
      (node (ref "U8") (pin "27") (pinfunction "PGA0_DP/ADC0_DP0/ADC1_DP3_._27") (pintype "bidirectional"))
    )
    (net (code "27") (name "/L1PH") (class "Default")
      (node (ref "U8") (pin "111") (pinfunction "PTC6/LLWU_P10_._CMP0_IN0_._SPI0_SOUT_._PDB0_EXTRG_._I2S0_RX#CLK_._FB_AD9/NFC_DATA6_._I2S0_MCLK_._111") (pintype "bidirectional"))
    )
    (net (code "28") (name "/L1SW") (class "Default")
      (node (ref "U8") (pin "142") (pinfunction "PTD13_._SPI2_SOUT_._SDHC0_D5_._FB_A21_._142") (pintype "bidirectional"))
    )
    (net (code "29") (name "/L1V") (class "Default")
      (node (ref "U8") (pin "28") (pinfunction "PGA0_DM/ADC0_DM0/ADC1_DM3_._28") (pintype "bidirectional"))
    )
    (net (code "30") (name "/L2CTRL") (class "Default")
      (node (ref "U8") (pin "128") (pinfunction "PTD1_._ADC0_SE5b_._SPI0_SCK_._UART2_CTS#_._FTM3_CH1_._FB_CS0#_._I2S1_RXD0_._128") (pintype "bidirectional"))
    )
    (net (code "31") (name "/L2DET") (class "Default")
      (node (ref "U8") (pin "132") (pinfunction "PTD5_._ADC0_SE6b_._SPI0_PCS2_._UART0_CTS#_._FTM0_CH5_._FB_AD1/NFC_DATA0_._EWM_OUT#_._132") (pintype "bidirectional"))
    )
    (net (code "32") (name "/L2I") (class "Default")
      (node (ref "U8") (pin "29") (pinfunction "PGA1_DP/ADC1_DP0/ADC0_DP3_._29") (pintype "bidirectional"))
    )
    (net (code "33") (name "/L2PH") (class "Default")
      (node (ref "U8") (pin "105") (pinfunction "PTC2_._ADC0_SE4b/CMP1_IN0/TSI0_CH15_._SPI0_PCS2_._UART1_CTS#_._FTM0_CH1_._FB_AD12/NFC_DATA9_._I2S0_TX_FS_._105") (pintype "bidirectional"))
    )
    (net (code "34") (name "/L2SW") (class "Default")
      (node (ref "U8") (pin "143") (pinfunction "PTD14_._SPI2_SIN_._SDHC0_D6_._FB_A22_._143") (pintype "bidirectional"))
    )
    (net (code "35") (name "/L2V") (class "Default")
      (node (ref "U8") (pin "30") (pinfunction "PGA1_DM/ADC1_DM0/ADC0_DM3_._30") (pintype "bidirectional"))
    )
    (net (code "36") (name "/L3CTRL") (class "Default")
      (node (ref "U8") (pin "129") (pinfunction "PTD2/LLWU_P13_._SPI0_SOUT_._UART2_RX_._FTM3_CH2_._FB_AD4_._I2S1_RX_FS_._129") (pintype "bidirectional"))
    )
    (net (code "37") (name "/L3DET") (class "Default")
      (node (ref "U8") (pin "133") (pinfunction "PTD6/LLWU_P15_._ADC0_SE7b_._SPI0_PCS3_._UART0_RX_._FTM0_CH6_._FB_AD0_._FTM0_FLT0_._133") (pintype "bidirectional"))
    )
    (net (code "38") (name "/L3I") (class "Default")
      (node (ref "U8") (pin "23") (pinfunction "PGA2_DP/ADC2_DP0/ADC3_DP3/ADC0_DP1_._23") (pintype "bidirectional"))
    )
    (net (code "39") (name "/L3PH") (class "Default")
      (node (ref "U8") (pin "64") (pinfunction "PTA12_._CMP2_IN0_._CAN0_TX_._FTM1_CH0_._RMII0_RXD1/MII0_RXD1_._I2S0_TXD0_._FTM1_QD_PHA_._64") (pintype "bidirectional"))
    )
    (net (code "40") (name "/L3SW") (class "Default")
      (node (ref "U8") (pin "144") (pinfunction "PTD15_._SPI2_PCS1_._SDHC0_D7_._FB_A23_._144") (pintype "bidirectional"))
    )
    (net (code "41") (name "/L3V") (class "Default")
      (node (ref "U8") (pin "24") (pinfunction "PGA2_DM/ADC2_DM0/ADC3_DM3/ADC0_DM1_._24") (pintype "bidirectional"))
    )
    (net (code "42") (name "/LAND1") (class "Default")
      (node (ref "U8") (pin "80") (pinfunction "PTA29_._ADC2_SE12_._ULPI_DATA7_._MII0_COL_._FB_A24_._80") (pintype "bidirectional"))
    )
    (net (code "43") (name "/LAND2") (class "Default")
      (node (ref "U8") (pin "79") (pinfunction "PTA28_._ADC2_SE13_._ULPI_DATA6_._MII0_TXER_._FB_A25_._79") (pintype "bidirectional"))
    )
    (net (code "44") (name "/LAND3") (class "Default")
      (node (ref "U8") (pin "78") (pinfunction "PTA27_._ADC2_SE14_._ULPI_DATA5_._MII0_CRS_._FB_A26_._78") (pintype "bidirectional"))
    )
    (net (code "45") (name "/LAND4") (class "Default")
      (node (ref "U8") (pin "77") (pinfunction "PTA26_._ADC2_SE15_._ULPI_DATA4_._MII0_TXD3_._FB_A27_._77") (pintype "bidirectional"))
    )
    (net (code "46") (name "/LAND5") (class "Default")
      (node (ref "U8") (pin "11") (pinfunction "PTE8_._ADC2_SE16_._I2S0_RXD1_._UART5_TX_._I2S0_RX_FS_._FTM3_CH3_._11") (pintype "bidirectional"))
    )
    (net (code "47") (name "/LAND6") (class "Default")
      (node (ref "U8") (pin "12") (pinfunction "PTE9_._ADC2_SE17_._I2S0_TXD1_._UART5_RX_._I2S0_RX#CLK_._FTM3_CH4_._12") (pintype "bidirectional"))
    )
    (net (code "48") (name "/MISCSW1") (class "Default")
      (node (ref "U8") (pin "14") (pinfunction "PTE11_._ADC3_SE16_._UART5_RTS#_._I2S0_TX_FS_._FTM3_CH6_._14") (pintype "bidirectional"))
    )
    (net (code "49") (name "/MISCSW2") (class "Default")
      (node (ref "U8") (pin "15") (pinfunction "PTE12_._ADC3_SE17_._I2S0_TX#CLK_._FTM3_CH7_._15") (pintype "bidirectional"))
    )
    (net (code "50") (name "/MOTOR_TEMP") (class "Default")
      (node (ref "U8") (pin "25") (pinfunction "PGA3_DP/ADC3_DP0/ADC2_DP3/ADC1_DP1_._25") (pintype "bidirectional"))
    )
    (net (code "51") (name "/OIL") (class "Default")
      (node (ref "U8") (pin "65") (pinfunction "PTA13/LLWU_P4_._CMP2_IN1_._CAN0_RX_._FTM1_CH1_._RMII0_RXD0/MII0_RXD0_._I2S0_TX_FS_._FTM1_QD_PHB_._65") (pintype "bidirectional"))
    )
    (net (code "52") (name "/OUT1") (class "Default")
      (node (ref "U8") (pin "82") (pinfunction "PTB1_._ADC0-3_SE9/TSI0_CH6_._I2C0_SDA_._FTM1_CH1_._RMII0_MDC/MII0_MDC_._FTM1_QD_PHB_._82") (pintype "bidirectional"))
    )
    (net (code "53") (name "/OUT2") (class "Default")
      (node (ref "U8") (pin "83") (pinfunction "PTB2_._ADC0_SE12/TSI0_CH7_._I2C0_SCL_._UART0_RTS#_._ENET0_1588_TMR0_._FTM0_FLT3_._83") (pintype "bidirectional"))
    )
    (net (code "54") (name "/OUT3") (class "Default")
      (node (ref "U8") (pin "84") (pinfunction "PTB3_._ADC0_SE13/TSI0_CH8_._I2C0_SDA_._UART0_CTS#/UART0_COL#_._ENET0_1588_TMR1_._FTM0_FLT0_._84") (pintype "bidirectional"))
    )
    (net (code "55") (name "/OUT4") (class "Default")
      (node (ref "U8") (pin "85") (pinfunction "PTB4_._ADC1_SE10_._ENET0_1588_TMR2_._FTM1_FLT0_._85") (pintype "bidirectional"))
    )
    (net (code "56") (name "/OUT5") (class "Default")
      (node (ref "U8") (pin "86") (pinfunction "PTB5_._ADC1_SE11_._ENET0_1588_TMR3_._FTM2_FLT0_._86") (pintype "bidirectional"))
    )
    (net (code "57") (name "/OUT6") (class "Default")
      (node (ref "U8") (pin "87") (pinfunction "PTB6_._ADC1_SE12_._FB_AD23_._87") (pintype "bidirectional"))
    )
    (net (code "58") (name "/OUT7") (class "Default")
      (node (ref "U8") (pin "88") (pinfunction "PTB7_._ADC1_SE13_._FB_AD22_._88") (pintype "bidirectional"))
    )
    (net (code "59") (name "/PSENS1") (class "Default")
      (node (ref "U8") (pin "60") (pinfunction "PTA8_._ADC0_SE11_._ULPI_NXT_._FTM1_CH0_._I2S1_RX_FS_._FTM1_QD_PHA_._TRACE_D2_._60") (pintype "bidirectional"))
    )
    (net (code "60") (name "/PSENS2") (class "Default")
      (node (ref "U8") (pin "61") (pinfunction "PTA9_._ADC3_SE5a_._ULPI_STP_._FTM1_CH1_._MII0_RXD3_._FTM1_QD_PHB_._TRACE_D1_._61") (pintype "bidirectional"))
    )
    (net (code "61") (name "/REFSW") (class "Default")
      (node (ref "U8") (pin "47") (pinfunction "PTE26_._ADC3_SE5b_._ENET_1588_CLKIN_._UART4_CTS#_._I2S1_TXD0_._RTC_CLKOUT_._USB_CLKIN_._47") (pintype "bidirectional"))
    )
    (net (code "62") (name "/RESET") (class "Default")
      (node (ref "C65") (pin "2") (pinfunction "2_2") (pintype "passive"))
      (node (ref "R84") (pin "2") (pinfunction "2_2") (pintype "passive"))
      (node (ref "U8") (pin "74") (pinfunction "RESET#_._74") (pintype "input"))
      (node (ref "X26") (pin "8") (pinfunction "RESET_8") (pintype "output"))
    )
    (net (code "63") (name "/REVERSE") (class "Default")
      (node (ref "U8") (pin "59") (pinfunction "PTA7_._ADC0_SE10_._ULPI_DIR_._FTM0_CH4_._I2S1_RX#CLK_._TRACE_D3_._59") (pintype "bidirectional"))
    )
    (net (code "64") (name "/RS485A") (class "Default")
      (node (ref "R26") (pin "2") (pinfunction "2_2") (pintype "passive"))
      (node (ref "U3") (pin "6") (pinfunction "A_6") (pintype "bidirectional"))
    )
    (net (code "65") (name "/RS485B") (class "Default")
      (node (ref "J3") (pin "1") (pinfunction "1_1") (pintype "passive"))
      (node (ref "U3") (pin "7") (pinfunction "B_7") (pintype "bidirectional"))
    )
    (net (code "66") (name "/SD_CLK") (class "Default")
      (node (ref "U8") (pin "3") (pinfunction "PTE2/LLWU_P1_._ADC1_SE6a_._SPI1_SCK_._UART1_CTS#_._SDHC0_DCLK_._3") (pintype "bidirectional"))
      (node (ref "X17") (pin "5") (pinfunction "CLK/SCLK_5") (pintype "passive"))
    )
    (net (code "67") (name "/SD_CMD") (class "Default")
      (node (ref "U8") (pin "4") (pinfunction "PTE3_._ADC1_SE7a_._SPI1_SIN_._UART1_RTS#_._SDHC0_CMD_._SPI1_SOUT_._4") (pintype "bidirectional"))
      (node (ref "X17") (pin "3") (pinfunction "CMD/DI_3") (pintype "passive"))
    )
    (net (code "68") (name "/SD_D0") (class "Default")
      (node (ref "U8") (pin "2") (pinfunction "PTE1/LLWU_P0_._ADC1_SE5a_._SPI1_SOUT_._UART1_RX_._SDHC0_D0_._I2C1_SCL_._SPI1_SIN_._2") (pintype "bidirectional"))
      (node (ref "X17") (pin "7") (pinfunction "DAT0/DO_7") (pintype "passive"))
    )
    (net (code "69") (name "/SD_D1") (class "Default")
      (node (ref "U8") (pin "1") (pinfunction "PTE0_._ADC1_SE4a_._SPI1_PCS1_._UART1_TX_._SDHC0_D1_._I2C1_SDA_._RTC_CLKOUT_._1") (pintype "bidirectional"))
      (node (ref "X17") (pin "8") (pinfunction "DAT1_8") (pintype "passive"))
    )
    (net (code "70") (name "/SD_D2") (class "Default")
      (node (ref "U8") (pin "8") (pinfunction "PTE5_._SPI1_PCS2_._UART3_RX_._SDHC0_D2_._FTM3_CH0_._8") (pintype "bidirectional"))
      (node (ref "X17") (pin "1") (pinfunction "DAT2_1") (pintype "passive"))
    )
    (net (code "71") (name "/SD_D3") (class "Default")
      (node (ref "U8") (pin "7") (pinfunction "PTE4/LLWU_P2_._SPI1_PCS0_._UART3_TX_._SDHC0_D3_._7") (pintype "bidirectional"))
      (node (ref "X17") (pin "2") (pinfunction "CD/DAT3/CS_2") (pintype "passive"))
    )
    (net (code "72") (name "/SOL1_STATE") (class "Default")
      (node (ref "U8") (pin "35") (pinfunction "ADC1_SE16/CMP2_IN2/ADC0_SE22_._35") (pintype "bidirectional"))
    )
    (net (code "73") (name "/SOL2_STATE") (class "Default")
      (node (ref "U8") (pin "36") (pinfunction "ADC0_SE16/CMP1_IN2/ADC0_SE21_._36") (pintype "bidirectional"))
    )
    (net (code "74") (name "/SOLENOID1") (class "Default")
      (node (ref "U8") (pin "63") (pinfunction "PTA11_._ADC3_SE15_._ULPI_DATA1_._FTM2_CH1_._MII0_RXCLK_._FTM2_QD_PHB_._63") (pintype "bidirectional"))
    )
    (net (code "75") (name "/SOLENOID2") (class "Default")
      (node (ref "U8") (pin "62") (pinfunction "PTA10_._ADC3_SE4a_._ULPI_DATA0_._FTM2_CH0_._MII0_RXD2_._FTM2_QD_PHA_._TRACE_D0_._62") (pintype "bidirectional"))
    )
    (net (code "76") (name "/SPI0_PCS0") (class "Default")
      (node (ref "U8") (pin "109") (pinfunction "PTC4/LLWU_P8_._SPI0_PCS0_._UART1_TX_._FTM0_CH3_._FB_AD11/NFC_DATA8_._CMP1_OUT_._I2S1_TX#CLK_._109") (pintype "bidirectional"))
    )
    (net (code "77") (name "/SPI0_SCK") (class "Default")
      (node (ref "U8") (pin "110") (pinfunction "PTC5/LLWU_P9_._SPI0_SCK_._LPTMR0_ALT2_._I2S0_RXD0_._FB_AD10/NFC_DATA7_._CMP0_OUT_._I2S1_TX_FS_._110") (pintype "bidirectional"))
    )
    (net (code "78") (name "/SPI0_SIN") (class "Default")
      (node (ref "U8") (pin "112") (pinfunction "PTC7_._CMP0_IN1_._SPI0_SIN_._USB_SOF_OUT_._I2S0_RX_FS_._FB_AD8/NFC_DATA5_._112") (pintype "bidirectional"))
    )
    (net (code "79") (name "/SPI0_SOUT") (class "Default")
      (node (ref "U8") (pin "68") (pinfunction "PTA16_._CMP3_IN2_._SPI0_SOUT_._UART0_CTS#/UART0_COL#_._RMII0_TXD0/MII0_TXD0_._I2S0_RX_FS_._I2S0_RXD1_._68") (pintype "bidirectional"))
    )
    (net (code "80") (name "/SPI2_CLK") (class "Default")
      (node (ref "U11") (pin "2") (pinfunction "SCK_2") (pintype "passive"))
      (node (ref "U8") (pin "100") (pinfunction "PTB21_._ADC2_SE5a_._SPI2_SCK_._FB_AD30/NFC_DATA14_._CMP1_OUT_._100") (pintype "bidirectional"))
    )
    (net (code "81") (name "/SPI2_CS") (class "Default")
      (node (ref "U11") (pin "4") (pinfunction "~{CS}_4") (pintype "passive"))
      (node (ref "U8") (pin "99") (pinfunction "PTB20_._ADC2_SE4a_._SPI2_PCS0_._FB_AD31/NFC_DATA15_._CMP0_OUT_._99") (pintype "bidirectional"))
    )
    (net (code "82") (name "/SPI2_SIN") (class "Default")
      (node (ref "U11") (pin "8") (pinfunction "SO_8") (pintype "passive"))
      (node (ref "U8") (pin "102") (pinfunction "PTB23_._SPI2_SIN_._SPI0_PCS5_._FB_AD28/NFC_DATA12_._CMP3_OUT_._102") (pintype "bidirectional"))
    )
    (net (code "83") (name "/SPI2_SOUT") (class "Default")
      (node (ref "U11") (pin "1") (pinfunction "SI_1") (pintype "passive"))
      (node (ref "U8") (pin "101") (pinfunction "PTB22_._SPI2_SOUT_._FB_AD29/NFC_DATA13_._CMP2_OUT_._101") (pintype "bidirectional"))
    )
    (net (code "84") (name "/SPI_RES") (class "Default")
      (node (ref "U11") (pin "3") (pinfunction "~{RESET}_3") (pintype "passive"))
      (node (ref "U8") (pin "103") (pinfunction "PTC0_._ADC0_SE14/TSI0_CH13_._SPI0_PCS4_._PDB0_EXTRG_._FB_AD14/NFC_DATA11_._I2S0_TXD1_._103") (pintype "bidirectional"))
    )
    (net (code "85") (name "/UART0_RTS") (class "Default")
      (node (ref "U3") (pin "3") (pinfunction "DE_3") (pintype "input"))
      (node (ref "U8") (pin "69") (pinfunction "PTA17_._ADC1_SE17_._SPI0_SIN_._UART0_RTS#_._RMII0_TXD1/MII0_TXD1_._I2S0_MCLK_._69") (pintype "bidirectional"))
    )
    (net (code "86") (name "/UART0_RX") (class "Default")
      (node (ref "U3") (pin "1") (pinfunction "RO_1") (pintype "output"))
      (node (ref "U8") (pin "67") (pinfunction "PTA15_._CMP3_IN1_._SPI0_SCK_._UART0_RX_._RMII0_TXEN/MII0_TXEN_._I2S0_RXD0_._67") (pintype "bidirectional"))
    )
    (net (code "87") (name "/UART0_TX") (class "Default")
      (node (ref "U3") (pin "4") (pinfunction "DI_4") (pintype "input"))
      (node (ref "U8") (pin "66") (pinfunction "PTA14_._CMP3_IN0_._SPI0_PCS0_._UART0_TX_._RMII0_CRS_DV/MII0_RXDV_._I2S0_RX#CLK_._I2S0_TXD1_._66") (pintype "bidirectional"))
    )
    (net (code "88") (name "/UART3_RX") (class "Default")
      (node (ref "U17") (pin "9") (pinfunction "R2OUT_9") (pintype "passive"))
      (node (ref "U8") (pin "91") (pinfunction "PTB10_._ADC1_SE14_._SPI1_PCS0_._UART3_RX_._I2S1_TX#CLK_._FB_AD19_._FTM0_FLT1_._91") (pintype "bidirectional"))
    )
    (net (code "89") (name "/UART3_TX") (class "Default")
      (node (ref "U17") (pin "10") (pinfunction "T2IN_10") (pintype "passive"))
      (node (ref "U8") (pin "92") (pinfunction "PTB11_._ADC1_SE15_._SPI1_SCK_._UART3_TX_._I2S1_TX_FS_._FB_AD18_._FTM0_FLT2_._92") (pintype "bidirectional"))
    )
    (net (code "90") (name "/UART4_RX") (class "Default")
      (node (ref "U8") (pin "119") (pinfunction "PTC14_._UART4_RX_._FB_AD25_._119") (pintype "bidirectional"))
    )
    (net (code "91") (name "/UART4_TX") (class "Default")
      (node (ref "U8") (pin "120") (pinfunction "PTC15_._UART4_TX_._FB_AD24_._120") (pintype "bidirectional"))
    )
    (net (code "92") (name "/UART5_RX") (class "Default")
      (node (ref "U17") (pin "12") (pinfunction "R1OUT_12") (pintype "passive"))
      (node (ref "U8") (pin "137") (pinfunction "PTD8_._I2C0_SCL_._UART5_RX_._FB_A16/NFC_CLE_._137") (pintype "bidirectional"))
    )
    (net (code "93") (name "/UART5_TX") (class "Default")
      (node (ref "U17") (pin "11") (pinfunction "T1IN_11") (pintype "passive"))
      (node (ref "U8") (pin "138") (pinfunction "PTD9_._I2C0_SDA_._UART5_TX_._FB_A17/NFC_ALE_._138") (pintype "bidirectional"))
    )
    (net (code "94") (name "/UPLSW") (class "Default")
      (node (ref "U8") (pin "45") (pinfunction "PTE24_._ADC0_SE17/EXTAL1_._CAN1_TX_._UART4_TX_._I2S1_TX_FS_._EWM_OUT#_._I2S1_RXD1_._45") (pintype "bidirectional"))
    )
    (net (code "95") (name "/WEARSW") (class "Default")
      (node (ref "U8") (pin "46") (pinfunction "PTE25_._ADC0_SE18/XTAL1_._CAN1_RX_._UART4_RX_._I2S1_TX#CLK_._EWM_IN_._I2S1_TXD1_._46") (pintype "bidirectional"))
    )
    (net (code "96") (name "/WIFI_IRQ") (class "Default")
      (node (ref "U8") (pin "54") (pinfunction "PTA4/LLWU_P3_._TSI0_CH5_._FTM0_CH1_._NMI#_._EZP_CS#_54") (pintype "bidirectional"))
    )
    (net (code "97") (name "/WIFI_RESET") (class "Default")
      (node (ref "U8") (pin "106") (pinfunction "PTC3/LLWU_P7_._CMP1_IN1_._SPI0_PCS1_._UART1_RX_._FTM0_CH2_._CLKOUT_._I2S0_TX#CLK_._106") (pintype "bidirectional"))
    )
    (net (code "98") (name "/WIFI_nHIB") (class "Default")
      (node (ref "U8") (pin "49") (pinfunction "PTE28_._ADC3_SE7a_._49") (pintype "bidirectional"))
    )
    (net (code "99") (name "/XTAL") (class "Default")
      (node (ref "C63") (pin "1") (pinfunction "1_1") (pintype "passive"))
      (node (ref "R81") (pin "1") (pinfunction "1_1") (pintype "passive"))
      (node (ref "U8") (pin "73") (pinfunction "PTA19_._XTAL0_._FTM1_FLT0_._FTM_CLKIN1_._LPTMR0_ALT1_._73") (pintype "bidirectional"))
      (node (ref "Z1") (pin "1") (pinfunction "1_1") (pintype "passive"))
    )
    (net (code "100") (name "AGND") (class "Default")
      (node (ref "C49") (pin "2") (pinfunction "2_2") (pintype "passive"))
      (node (ref "C50") (pin "2") (pinfunction "2_2") (pintype "passive"))
      (node (ref "C55") (pin "2") (pinfunction "2_2") (pintype "passive"))
      (node (ref "L8") (pin "1") (pinfunction "1_1") (pintype "passive"))
      (node (ref "L9") (pin "2") (pinfunction "2_2") (pintype "passive"))
      (node (ref "U8") (pin "34") (pinfunction "VSSA_._34") (pintype "power_in"))
    )
    (net (code "101") (name "GND") (class "Default")
      (node (ref "B1") (pin "1") (pinfunction "1_1") (pintype "passive"))
      (node (ref "C18") (pin "2") (pinfunction "2_2") (pintype "passive"))
      (node (ref "C30") (pin "2") (pinfunction "2_2") (pintype "passive"))
      (node (ref "C31") (pin "2") (pinfunction "2_2") (pintype "passive"))
      (node (ref "C38") (pin "1") (pinfunction "1_1") (pintype "passive"))
      (node (ref "C39") (pin "1") (pinfunction "1_1") (pintype "passive"))
      (node (ref "C40") (pin "1") (pinfunction "1_1") (pintype "passive"))
      (node (ref "C41") (pin "2") (pinfunction "2_2") (pintype "passive"))
      (node (ref "C42") (pin "1") (pinfunction "1_1") (pintype "passive"))
      (node (ref "C43") (pin "2") (pinfunction "2_2") (pintype "passive"))
      (node (ref "C45") (pin "2") (pinfunction "2_2") (pintype "passive"))
      (node (ref "C46") (pin "1") (pinfunction "1_1") (pintype "passive"))
      (node (ref "C47") (pin "1") (pinfunction "1_1") (pintype "passive"))
      (node (ref "C56") (pin "1") (pinfunction "1_1") (pintype "passive"))
      (node (ref "C57") (pin "1") (pinfunction "1_1") (pintype "passive"))
      (node (ref "C58") (pin "1") (pinfunction "1_1") (pintype "passive"))
      (node (ref "C61") (pin "2") (pinfunction "2_2") (pintype "passive"))
      (node (ref "C62") (pin "2") (pinfunction "2_2") (pintype "passive"))
      (node (ref "C63") (pin "2") (pinfunction "2_2") (pintype "passive"))
      (node (ref "C64") (pin "2") (pinfunction "2_2") (pintype "passive"))
      (node (ref "C65") (pin "1") (pinfunction "1_1") (pintype "passive"))
      (node (ref "C66") (pin "2") (pinfunction "2_2") (pintype "passive"))
      (node (ref "C76") (pin "2") (pinfunction "2_2") (pintype "passive"))
      (node (ref "C77") (pin "2") (pinfunction "2_2") (pintype "passive"))
      (node (ref "C78") (pin "2") (pinfunction "2_2") (pintype "passive"))
      (node (ref "C80") (pin "1") (pinfunction "1_1") (pintype "passive"))
      (node (ref "C88") (pin "2") (pinfunction "2_2") (pintype "passive"))
      (node (ref "L9") (pin "1") (pinfunction "1_1") (pintype "passive"))
      (node (ref "R79") (pin "1") (pinfunction "1_1") (pintype "passive"))
      (node (ref "SW1") (pin "5") (pinfunction "5_5") (pintype "passive"))
      (node (ref "SW1") (pin "6") (pinfunction "6_6") (pintype "passive"))
      (node (ref "SW1") (pin "7") (pinfunction "7_7") (pintype "passive"))
      (node (ref "SW1") (pin "8") (pinfunction "8_8") (pintype "passive"))
      (node (ref "U11") (pin "7") (pinfunction "GND_7") (pintype "passive"))
      (node (ref "U15") (pin "2") (pinfunction "GND_2") (pintype "power_in"))
      (node (ref "U15") (pin "8") (pinfunction "RS_8") (pintype "input"))
      (node (ref "U17") (pin "15") (pinfunction "GND_15") (pintype "passive"))
      (node (ref "U3") (pin "2") (pinfunction "~{RE}_2") (pintype "input"))
      (node (ref "U3") (pin "5") (pinfunction "GND_5") (pintype "power_in"))
      (node (ref "U8") (pin "107") (pinfunction "VSS_._107") (pintype "power_in"))
      (node (ref "U8") (pin "121") (pinfunction "VSS_._121") (pintype "power_in"))
      (node (ref "U8") (pin "134") (pinfunction "VSS_._134") (pintype "power_in"))
      (node (ref "U8") (pin "17") (pinfunction "VSS_._17") (pintype "power_in"))
      (node (ref "U8") (pin "44") (pinfunction "VSS_._44") (pintype "power_in"))
      (node (ref "U8") (pin "57") (pinfunction "VSS_._57") (pintype "power_in"))
      (node (ref "U8") (pin "6") (pinfunction "VSS_._6") (pintype "power_in"))
      (node (ref "U8") (pin "71") (pinfunction "VSS_._71") (pintype "power_in"))
      (node (ref "U8") (pin "93") (pinfunction "VSS_._93") (pintype "power_in"))
      (node (ref "X17") (pin "10") (pinfunction "WP_10") (pintype "passive"))
      (node (ref "X17") (pin "11") (pinfunction "GND_11") (pintype "passive"))
      (node (ref "X17") (pin "12") (pinfunction "GND_12") (pintype "passive"))
      (node (ref "X17") (pin "6") (pinfunction "VSS2_6") (pintype "passive"))
      (node (ref "X17") (pin "9") (pintype "passive"))
      (node (ref "X26") (pin "1") (pinfunction "GND_1") (pintype "power_in"))
      (node (ref "X26") (pin "10") (pinfunction "GND_10") (pintype "power_in"))
      (node (ref "X26") (pin "6") (pinfunction "RTCK_6") (pintype "input"))
      (node (ref "X37") (pin "1") (pinfunction "COM_1") (pintype "passive"))
      (node (ref "X38") (pin "1") (pinfunction "COM_1") (pintype "passive"))
    )
    (net (code "102") (name "Net-(B1-Pad2)") (class "Default")
      (node (ref "B1") (pin "2") (pinfunction "2_2") (pintype "passive"))
      (node (ref "R92") (pin "2") (pinfunction "2_2") (pintype "passive"))
    )
    (net (code "103") (name "Net-(C55-Pad1)") (class "Default")
      (node (ref "C55") (pin "1") (pinfunction "1_1") (pintype "passive"))
      (node (ref "R77") (pin "1") (pinfunction "1_1") (pintype "passive"))
    )
    (net (code "104") (name "Net-(J3-Pad2)") (class "Default")
      (node (ref "J3") (pin "2") (pinfunction "2_2") (pintype "passive"))
      (node (ref "R26") (pin "1") (pinfunction "1_1") (pintype "passive"))
    )
    (net (code "105") (name "Net-(J7-Pad2)") (class "Default")
      (node (ref "J7") (pin "2") (pinfunction "2_2") (pintype "passive"))
      (node (ref "R105") (pin "1") (pinfunction "1_1") (pintype "passive"))
    )
    (net (code "106") (name "Net-(U8-EXTAL32_.)") (class "Default")
      (node (ref "C61") (pin "1") (pinfunction "1_1") (pintype "passive"))
      (node (ref "U8") (pin "41") (pinfunction "EXTAL32_._41") (pintype "bidirectional"))
      (node (ref "Z2") (pin "4") (pinfunction "4_4") (pintype "passive"))
    )
    (net (code "107") (name "Net-(U8-PTA5_._USB_CLKIN_._FTM0_CH2_._MII0_RXER_._CMP2_OUT_._I2S0_TX#CLK_._JTAG_TRST#_.)") (class "Default")
      (node (ref "TP1") (pin "1") (pinfunction "1_1") (pintype "passive"))
      (node (ref "U8") (pin "55") (pinfunction "PTA5_._USB_CLKIN_._FTM0_CH2_._MII0_RXER_._CMP2_OUT_._I2S0_TX#CLK_._JTAG_TRST#_._55") (pintype "bidirectional"))
    )
    (net (code "108") (name "Net-(U8-PTC16_._CAN1_RX_._UART3_RX_._ENET0_1588_TMR0_._FB_CS5#{slash}FB_TSIZ1{slash}FB#E23_16#_._NFC_RB_.)") (class "Default")
      (node (ref "SW1") (pin "1") (pinfunction "1_1") (pintype "passive"))
      (node (ref "U8") (pin "123") (pinfunction "PTC16_._CAN1_RX_._UART3_RX_._ENET0_1588_TMR0_._FB_CS5#/FB_TSIZ1/FB#E23_16#_._NFC_RB_._123") (pintype "bidirectional"))
    )
    (net (code "109") (name "Net-(U8-PTC17_._CAN1_TX_._UART3_TX_._ENET0_1588_TMR1_._FB_CS4#{slash}FB_TSIZ0{slash}FB#E31_24#_._NFC_CE0#_.)") (class "Default")
      (node (ref "SW1") (pin "2") (pinfunction "2_2") (pintype "passive"))
      (node (ref "U8") (pin "124") (pinfunction "PTC17_._CAN1_TX_._UART3_TX_._ENET0_1588_TMR1_._FB_CS4#/FB_TSIZ0/FB#E31_24#_._NFC_CE0#_._124") (pintype "bidirectional"))
    )
    (net (code "110") (name "Net-(U8-PTC18_._UART3_RTS#_._ENET0_1588_TMR2_._FB_TBST#{slash}FB_CS2#{slash}FB#E15_8#_._NFC_CE1#_.)") (class "Default")
      (node (ref "SW1") (pin "3") (pinfunction "3_3") (pintype "passive"))
      (node (ref "U8") (pin "125") (pinfunction "PTC18_._UART3_RTS#_._ENET0_1588_TMR2_._FB_TBST#/FB_CS2#/FB#E15_8#_._NFC_CE1#_._125") (pintype "bidirectional"))
    )
    (net (code "111") (name "Net-(U8-PTC19_._UART3_CTS#_._ENET0_1588_TMR3_._FB_CS3#{slash}FB#E7_0#_._FB_TA#_.)") (class "Default")
      (node (ref "SW1") (pin "4") (pinfunction "4_4") (pintype "passive"))
      (node (ref "U8") (pin "126") (pinfunction "PTC19_._UART3_CTS#_._ENET0_1588_TMR3_._FB_CS3#/FB#E7_0#_._FB_TA#_._126") (pintype "bidirectional"))
    )
    (net (code "112") (name "Net-(U8-VBAT_.)") (class "Default")
      (node (ref "D31") (pin "2") (pintype "passive"))
      (node (ref "R92") (pin "1") (pinfunction "1_1") (pintype "passive"))
      (node (ref "U8") (pin "42") (pinfunction "VBAT_._42") (pintype "power_in"))
    )
    (net (code "113") (name "Net-(U8-VDDA_.)") (class "Default")
      (node (ref "C49") (pin "1") (pinfunction "1_1") (pintype "passive"))
      (node (ref "C50") (pin "1") (pinfunction "1_1") (pintype "passive"))
      (node (ref "L6") (pin "2") (pinfunction "2_2") (pintype "passive"))
      (node (ref "L7") (pin "1") (pinfunction "1_1") (pintype "passive"))
      (node (ref "U8") (pin "31") (pinfunction "VDDA_._31") (pintype "power_in"))
    )
    (net (code "114") (name "Net-(U8-VOUT33_.)") (class "Default")
      (node (ref "C43") (pin "1") (pinfunction "1_1") (pintype "passive"))
      (node (ref "R69") (pin "1") (pinfunction "1_1") (pintype "passive"))
      (node (ref "U8") (pin "21") (pinfunction "VOUT33_._21") (pintype "bidirectional"))
    )
    (net (code "115") (name "Net-(U8-VREFH_.)") (class "Default")
      (node (ref "C52") (pin "2") (pinfunction "2_2") (pintype "passive"))
      (node (ref "C53") (pin "2") (pinfunction "2_2") (pintype "passive"))
      (node (ref "L7") (pin "2") (pinfunction "2_2") (pintype "passive"))
      (node (ref "U8") (pin "32") (pinfunction "VREFH_._32") (pintype "power_in"))
    )
    (net (code "116") (name "Net-(U8-VREFL_.)") (class "Default")
      (node (ref "C52") (pin "1") (pinfunction "1_1") (pintype "passive"))
      (node (ref "C53") (pin "1") (pinfunction "1_1") (pintype "passive"))
      (node (ref "L8") (pin "2") (pinfunction "2_2") (pintype "passive"))
      (node (ref "U8") (pin "33") (pinfunction "VREFL_._33") (pintype "power_in"))
    )
    (net (code "117") (name "Net-(U8-VREF_OUT{slash}CMP1_IN5{slash}CMP0_IN5{slash}ADC1_SE18_.)") (class "Default")
      (node (ref "R77") (pin "2") (pinfunction "2_2") (pintype "passive"))
      (node (ref "U8") (pin "37") (pinfunction "VREF_OUT/CMP1_IN5/CMP0_IN5/ADC1_SE18_._37") (pintype "bidirectional"))
    )
    (net (code "118") (name "Net-(U8-VREGIN_.)") (class "Default")
      (node (ref "R71") (pin "2") (pinfunction "2_2") (pintype "passive"))
      (node (ref "U8") (pin "22") (pinfunction "VREGIN_._22") (pintype "input"))
    )
    (net (code "119") (name "Net-(U8-XTAL32_.)") (class "Default")
      (node (ref "C62") (pin "1") (pinfunction "1_1") (pintype "passive"))
      (node (ref "U8") (pin "40") (pinfunction "XTAL32_._40") (pintype "bidirectional"))
      (node (ref "Z2") (pin "1") (pinfunction "1_1") (pintype "passive"))
    )
    (net (code "120") (name "Net-(U17-C1+)") (class "Default")
      (node (ref "C79") (pin "1") (pinfunction "1_1") (pintype "passive"))
      (node (ref "U17") (pin "1") (pinfunction "C1+_1") (pintype "passive"))
    )
    (net (code "121") (name "Net-(U17-C1-)") (class "Default")
      (node (ref "C79") (pin "2") (pinfunction "2_2") (pintype "passive"))
      (node (ref "U17") (pin "3") (pinfunction "C1-_3") (pintype "passive"))
    )
    (net (code "122") (name "Net-(U17-C2+)") (class "Default")
      (node (ref "C84") (pin "1") (pinfunction "1_1") (pintype "passive"))
      (node (ref "U17") (pin "4") (pinfunction "C2+_4") (pintype "passive"))
    )
    (net (code "123") (name "Net-(U17-C2-)") (class "Default")
      (node (ref "C84") (pin "2") (pinfunction "2_2") (pintype "passive"))
      (node (ref "U17") (pin "5") (pinfunction "C2-_5") (pintype "passive"))
    )
    (net (code "124") (name "Net-(U17-R2IN)") (class "Default")
      (node (ref "U17") (pin "8") (pinfunction "R2IN_8") (pintype "passive"))
      (node (ref "X37") (pin "2") (pinfunction "RX_2") (pintype "passive"))
    )
    (net (code "125") (name "Net-(U17-T2OUT)") (class "Default")
      (node (ref "U17") (pin "7") (pinfunction "T2OUT_7") (pintype "passive"))
      (node (ref "X37") (pin "3") (pinfunction "TX_3") (pintype "passive"))
    )
    (net (code "126") (name "Net-(U17-V+)") (class "Default")
      (node (ref "C80") (pin "2") (pinfunction "2_2") (pintype "passive"))
      (node (ref "U17") (pin "2") (pinfunction "V+_2") (pintype "passive"))
    )
    (net (code "127") (name "Net-(U17-V-)") (class "Default")
      (node (ref "C88") (pin "1") (pinfunction "1_1") (pintype "passive"))
      (node (ref "U17") (pin "6") (pinfunction "V-_6") (pintype "passive"))
    )
    (net (code "128") (name "unconnected-(D31-Pad1)") (class "Default")
      (node (ref "D31") (pin "1") (pintype "passive"))
    )
    (net (code "129") (name "unconnected-(U8-DAC1_OUT{slash}CMP0_IN4{slash}CMP2_IN3{slash}ADC1_SE23_.-Pad39)") (class "Default")
      (node (ref "U8") (pin "39") (pinfunction "DAC1_OUT/CMP0_IN4/CMP2_IN3/ADC1_SE23_._39") (pintype "bidirectional"))
    )
    (net (code "130") (name "unconnected-(U8-PGA3_DM{slash}ADC3_DM0{slash}ADC2_DM3{slash}ADC1_DM1_.-Pad26)") (class "Default")
      (node (ref "U8") (pin "26") (pinfunction "PGA3_DM/ADC3_DM0/ADC2_DM3/ADC1_DM1_._26") (pintype "bidirectional"))
    )
    (net (code "131") (name "unconnected-(U8-PTA24_._CMP3_IN4_._ULPI_DATA2_._MII0_TXD2_._FB_A29_.-Pad75)") (class "Default")
      (node (ref "U8") (pin "75") (pinfunction "PTA24_._CMP3_IN4_._ULPI_DATA2_._MII0_TXD2_._FB_A29_._75") (pintype "bidirectional"))
    )
    (net (code "132") (name "unconnected-(U8-PTA25_._CMP3_IN5_._ULPI_DATA3_._MII0_TXCLK_._FB_A28_.-Pad76)") (class "Default")
      (node (ref "U8") (pin "76") (pinfunction "PTA25_._CMP3_IN5_._ULPI_DATA3_._MII0_TXCLK_._FB_A28_._76") (pintype "bidirectional"))
    )
    (net (code "133") (name "unconnected-(U8-PTB8_._UART3_RTS#_._FB_AD21_.-Pad89)") (class "Default")
      (node (ref "U8") (pin "89") (pinfunction "PTB8_._UART3_RTS#_._FB_AD21_._89") (pintype "bidirectional"))
    )
    (net (code "134") (name "unconnected-(U8-PTB9_._SPI1_PCS1_._UART3_CTS#_._FB_AD20_.-Pad90)") (class "Default")
      (node (ref "U8") (pin "90") (pinfunction "PTB9_._SPI1_PCS1_._UART3_CTS#_._FB_AD20_._90") (pintype "bidirectional"))
    )
    (net (code "135") (name "unconnected-(U8-PTB16_._TSI0_CH9_._SPI1_SOUT_._UART0_RX_._I2S1_TXD0_._FB_AD17_._EWM_IN_.-Pad95)") (class "Default")
      (node (ref "U8") (pin "95") (pinfunction "PTB16_._TSI0_CH9_._SPI1_SOUT_._UART0_RX_._I2S1_TXD0_._FB_AD17_._EWM_IN_._95") (pintype "bidirectional"))
    )
    (net (code "136") (name "unconnected-(U8-PTB17_._TSI0_CH10_._SPI1_SIN_._UART0_TX_._I2S1_TXD1_._FB_AD16_._EWM_OUT#_.-Pad96)") (class "Default")
      (node (ref "U8") (pin "96") (pinfunction "PTB17_._TSI0_CH10_._SPI1_SIN_._UART0_TX_._I2S1_TXD1_._FB_AD16_._EWM_OUT#_._96") (pintype "bidirectional"))
    )
    (net (code "137") (name "unconnected-(U8-PTC1{slash}LLWU_P6_._ADC0_SE15{slash}TSI0_CH14_._SPI0_PCS3_._UART1_RTS#_._FTM0_CH0_._FB_AD13{slash}NFC_DATA10_._I2S0_TXD0_.-Pad104)") (class "Default")
      (node (ref "U8") (pin "104") (pinfunction "PTC1/LLWU_P6_._ADC0_SE15/TSI0_CH14_._SPI0_PCS3_._UART1_RTS#_._FTM0_CH0_._FB_AD13/NFC_DATA10_._I2S0_TXD0_._104") (pintype "bidirectional"))
    )
    (net (code "138") (name "unconnected-(U8-PTC12_._UART4_RTS#_._FB_AD27_._FTM3_FLT0_.-Pad117)") (class "Default")
      (node (ref "U8") (pin "117") (pinfunction "PTC12_._UART4_RTS#_._FB_AD27_._FTM3_FLT0_._117") (pintype "bidirectional"))
    )
    (net (code "139") (name "unconnected-(U8-PTC13_._UART4_CTS#_._FB_AD26_.-Pad118)") (class "Default")
      (node (ref "U8") (pin "118") (pinfunction "PTC13_._UART4_CTS#_._FB_AD26_._118") (pintype "bidirectional"))
    )
    (net (code "140") (name "unconnected-(U8-PTD3_._SPI0_SIN_._UART2_TX_._FTM3_CH3_._FB_AD3_._I2S1_RX#CLK_.-Pad130)") (class "Default")
      (node (ref "U8") (pin "130") (pinfunction "PTD3_._SPI0_SIN_._UART2_TX_._FTM3_CH3_._FB_AD3_._I2S1_RX#CLK_._130") (pintype "bidirectional"))
    )
    (net (code "141") (name "unconnected-(U8-PTD7_._CMT_IRO_._UART0_TX_._FTM0_CH7_._FTM0_FLT1_.-Pad136)") (class "Default")
      (node (ref "U8") (pin "136") (pinfunction "PTD7_._CMT_IRO_._UART0_TX_._FTM0_CH7_._FTM0_FLT1_._136") (pintype "bidirectional"))
    )
    (net (code "142") (name "unconnected-(U8-PTE6_._SPI1_PCS3_._UART3_CTS#_._I2S0_MCLK_._FTM3_CH1_._USB_SOF_OUT_.-Pad9)") (class "Default")
      (node (ref "U8") (pin "9") (pinfunction "PTE6_._SPI1_PCS3_._UART3_CTS#_._I2S0_MCLK_._FTM3_CH1_._USB_SOF_OUT_._9") (pintype "bidirectional"))
    )
    (net (code "143") (name "unconnected-(U8-PTE7_._UART3_RTS#_._I2S0_RXD0_._FTM3_CH2_.-Pad10)") (class "Default")
      (node (ref "U8") (pin "10") (pinfunction "PTE7_._UART3_RTS#_._I2S0_RXD0_._FTM3_CH2_._10") (pintype "bidirectional"))
    )
    (net (code "144") (name "unconnected-(U8-PTE10_._UART5_CTS#_._I2S0_TXD0_._FTM3_CH5_.-Pad13)") (class "Default")
      (node (ref "U8") (pin "13") (pinfunction "PTE10_._UART5_CTS#_._I2S0_TXD0_._FTM3_CH5_._13") (pintype "bidirectional"))
    )
    (net (code "145") (name "unconnected-(U8-USB0_DM_.-Pad20)") (class "Default")
      (node (ref "U8") (pin "20") (pinfunction "USB0_DM_._20") (pintype "bidirectional"))
    )
    (net (code "146") (name "unconnected-(U8-USB0_DP_.-Pad19)") (class "Default")
      (node (ref "U8") (pin "19") (pinfunction "USB0_DP_._19") (pintype "bidirectional"))
    )
    (net (code "147") (name "unconnected-(U8-VSS_.-Pad18)") (class "Default")
      (node (ref "U8") (pin "18") (pinfunction "VSS_._18") (pintype "power_in"))
    )
    (net (code "148") (name "unconnected-(U15-VREF-Pad5)") (class "Default")
      (node (ref "U15") (pin "5") (pinfunction "VREF_5") (pintype "passive"))
    )
    (net (code "149") (name "unconnected-(X26-TRST-Pad2)") (class "Default")
      (node (ref "X26") (pin "2") (pinfunction "TRST_2") (pintype "passive"))
    )
  )
)
